# weichen-a-3.net
KiCad netlist of a schematic drawn in EAGLE
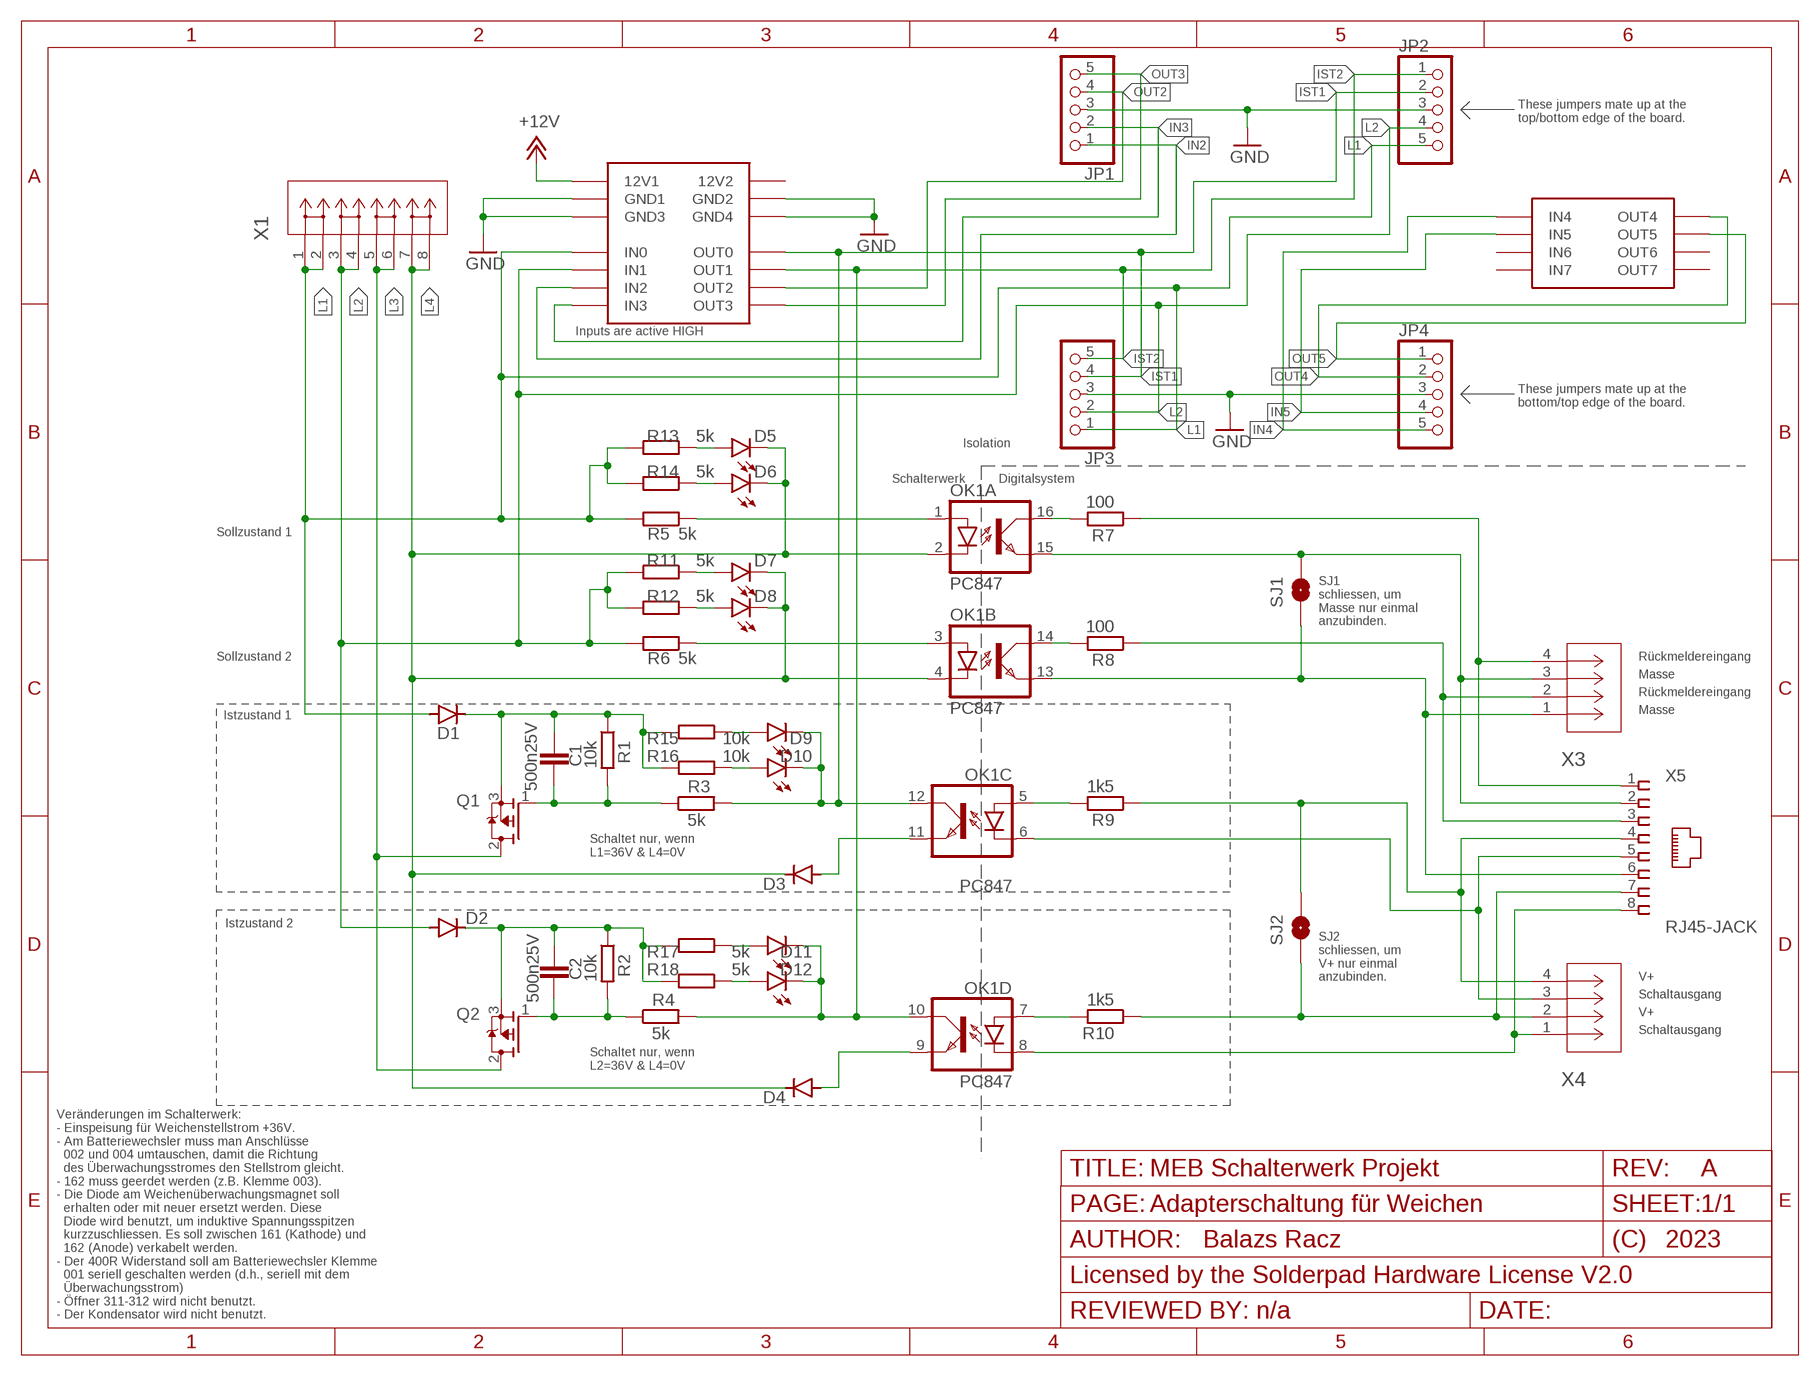
[diagram p0: schematic, sheet 1]

(export (version "E")
  (design (tool "Eeschema 10.0.6"))
  (components
    (comp (ref "C1")
      (value "500n25V")
      (footprint "eagle-import:C0805")
      (libsource (lib "eagle-import") (part "C-EUC0805"))
    )
    (comp (ref "C2")
      (value "500n25V")
      (footprint "eagle-import:C0805")
      (libsource (lib "eagle-import") (part "C-EUC0805"))
    )
    (comp (ref "D1")
      (value "DIODE-DO214AC")
      (footprint "eagle-import:DO214AC")
      (libsource (lib "eagle-import") (part "DIODE-DO214AC"))
    )
    (comp (ref "D2")
      (value "DIODE-DO214AC")
      (footprint "eagle-import:DO214AC")
      (libsource (lib "eagle-import") (part "DIODE-DO214AC"))
    )
    (comp (ref "D3")
      (value "DIODE-MINIMELF")
      (footprint "eagle-import:MINIMELF")
      (libsource (lib "eagle-import") (part "DIODE-MINIMELF"))
    )
    (comp (ref "D4")
      (value "DIODE-MINIMELF")
      (footprint "eagle-import:MINIMELF")
      (libsource (lib "eagle-import") (part "DIODE-MINIMELF"))
    )
    (comp (ref "D5")
      (value "LEDCHIPLED_0603")
      (footprint "eagle-import:CHIPLED_0603")
      (libsource (lib "eagle-import") (part "LEDCHIPLED_0603"))
    )
    (comp (ref "D6")
      (value "LEDHEADER")
      (footprint "eagle-import:LEDHEADER")
      (libsource (lib "eagle-import") (part "LEDHEADER"))
    )
    (comp (ref "D7")
      (value "LEDCHIPLED_0603")
      (footprint "eagle-import:CHIPLED_0603")
      (libsource (lib "eagle-import") (part "LEDCHIPLED_0603"))
    )
    (comp (ref "D8")
      (value "LEDHEADER")
      (footprint "eagle-import:LEDHEADER")
      (libsource (lib "eagle-import") (part "LEDHEADER"))
    )
    (comp (ref "D9")
      (value "LEDCHIPLED_0603")
      (footprint "eagle-import:CHIPLED_0603")
      (libsource (lib "eagle-import") (part "LEDCHIPLED_0603"))
    )
    (comp (ref "D10")
      (value "LEDHEADER")
      (footprint "eagle-import:LEDHEADER")
      (libsource (lib "eagle-import") (part "LEDHEADER"))
    )
    (comp (ref "D11")
      (value "LEDCHIPLED_0603")
      (footprint "eagle-import:CHIPLED_0603")
      (libsource (lib "eagle-import") (part "LEDCHIPLED_0603"))
    )
    (comp (ref "D12")
      (value "LEDHEADER")
      (footprint "eagle-import:LEDHEADER")
      (libsource (lib "eagle-import") (part "LEDHEADER"))
    )
    (comp (ref "JP1")
      (value "PINHD-1X55X2MM")
      (footprint "eagle-import:1_05X2MM")
      (libsource (lib "eagle-import") (part "PINHD-1X55X2MM"))
    )
    (comp (ref "JP2")
      (value "PINHD-1X55X2MM")
      (footprint "eagle-import:1_05X2MM")
      (libsource (lib "eagle-import") (part "PINHD-1X55X2MM"))
    )
    (comp (ref "JP3")
      (value "PINHD-1X55X2MM")
      (footprint "eagle-import:1_05X2MM")
      (libsource (lib "eagle-import") (part "PINHD-1X55X2MM"))
    )
    (comp (ref "JP4")
      (value "PINHD-1X55X2MM")
      (footprint "eagle-import:1_05X2MM")
      (libsource (lib "eagle-import") (part "PINHD-1X55X2MM"))
    )
    (comp (ref "OK1")
      (value "PC847")
      (footprint "eagle-import:DIL16")
      (libsource (lib "eagle-import") (part "PC847"))
    )
    (comp (ref "Q1")
      (value "P-MOSFET")
      (footprint "eagle-import:DPAK-2")
      (fields (field (name "MANUFACTURER") "Infineon"))
      (libsource (lib "eagle-import") (part "P-MOSFET"))
    )
    (comp (ref "Q2")
      (value "P-MOSFET")
      (footprint "eagle-import:DPAK-2")
      (fields (field (name "MANUFACTURER") "Infineon"))
      (libsource (lib "eagle-import") (part "P-MOSFET"))
    )
    (comp (ref "R1")
      (value "10k")
      (footprint "eagle-import:R0805")
      (libsource (lib "eagle-import") (part "R-EU_R0805"))
    )
    (comp (ref "R2")
      (value "10k")
      (footprint "eagle-import:R0805")
      (libsource (lib "eagle-import") (part "R-EU_R0805"))
    )
    (comp (ref "R3")
      (value "5k")
      (footprint "eagle-import:R0805")
      (libsource (lib "eagle-import") (part "R-EU_R0805"))
    )
    (comp (ref "R4")
      (value "5k")
      (footprint "eagle-import:R0805")
      (libsource (lib "eagle-import") (part "R-EU_R0805"))
    )
    (comp (ref "R5")
      (value "5k")
      (footprint "eagle-import:R0805")
      (libsource (lib "eagle-import") (part "R-EU_R0805"))
    )
    (comp (ref "R6")
      (value "5k")
      (footprint "eagle-import:R0805")
      (libsource (lib "eagle-import") (part "R-EU_R0805"))
    )
    (comp (ref "R7")
      (value "100")
      (footprint "eagle-import:R0805")
      (libsource (lib "eagle-import") (part "R-EU_R0805"))
    )
    (comp (ref "R8")
      (value "100")
      (footprint "eagle-import:R0805")
      (libsource (lib "eagle-import") (part "R-EU_R0805"))
    )
    (comp (ref "R9")
      (value "1k5")
      (footprint "eagle-import:R0805")
      (libsource (lib "eagle-import") (part "R-EU_R0805"))
    )
    (comp (ref "R10")
      (value "1k5")
      (footprint "eagle-import:R0805")
      (libsource (lib "eagle-import") (part "R-EU_R0805"))
    )
    (comp (ref "R11")
      (value "5k")
      (footprint "eagle-import:R0805")
      (libsource (lib "eagle-import") (part "R-EU_R0805"))
    )
    (comp (ref "R12")
      (value "5k")
      (footprint "eagle-import:R0805")
      (libsource (lib "eagle-import") (part "R-EU_R0805"))
    )
    (comp (ref "R13")
      (value "5k")
      (footprint "eagle-import:R0805")
      (libsource (lib "eagle-import") (part "R-EU_R0805"))
    )
    (comp (ref "R14")
      (value "5k")
      (footprint "eagle-import:R0805")
      (libsource (lib "eagle-import") (part "R-EU_R0805"))
    )
    (comp (ref "R15")
      (value "10k")
      (footprint "eagle-import:R0805")
      (libsource (lib "eagle-import") (part "R-EU_R0805"))
    )
    (comp (ref "R16")
      (value "10k")
      (footprint "eagle-import:R0805")
      (libsource (lib "eagle-import") (part "R-EU_R0805"))
    )
    (comp (ref "R17")
      (value "5k")
      (footprint "eagle-import:R0805")
      (libsource (lib "eagle-import") (part "R-EU_R0805"))
    )
    (comp (ref "R18")
      (value "5k")
      (footprint "eagle-import:R0805")
      (libsource (lib "eagle-import") (part "R-EU_R0805"))
    )
    (comp (ref "SJ1")
      (value "SJRND2")
      (footprint "eagle-import:SJ_RND2")
      (libsource (lib "eagle-import") (part "SJRND2"))
    )
    (comp (ref "SJ2")
      (value "SJRND2")
      (footprint "eagle-import:SJ_RND2")
      (libsource (lib "eagle-import") (part "SJRND2"))
    )
    (comp (ref "X1")
      (value "PHNX_4P_508CONN_1017493")
      (footprint "eagle-import:PHNX_4P_508")
      (fields
        (field (name "MANUFACTURER_PART_NUMBER") "1017505")
        (field (name "COPYRIGHT") "Copyright (C) 2023 Ultra Librarian. All rights reserved.")
      )
      (libsource (lib "eagle-import") (part "PHNX_4P_508CONN_1017493"))
    )
    (comp (ref "X2")
      (value "IO-HAT")
      (footprint "eagle-import:IOBOARD")
      (libsource (lib "eagle-import") (part "IO-HAT"))
    )
    (comp (ref "X3")
      (value "PHNX_4P_350CONN_1984989_PXC")
      (footprint "eagle-import:PHNX_4P_350")
      (fields
        (field (name "MANUFACTURER_PART_NUMBER") "1984989")
        (field (name "COPYRIGHT") "Copyright (C) 2023 Ultra Librarian. All rights reserved.")
      )
      (libsource (lib "eagle-import") (part "PHNX_4P_350CONN_1984989_PXC"))
    )
    (comp (ref "X4")
      (value "PHNX_4P_350CONN_1984989_PXC")
      (footprint "eagle-import:PHNX_4P_350")
      (fields
        (field (name "MANUFACTURER_PART_NUMBER") "1984989")
        (field (name "COPYRIGHT") "Copyright (C) 2023 Ultra Librarian. All rights reserved.")
      )
      (libsource (lib "eagle-import") (part "PHNX_4P_350CONN_1984989_PXC"))
    )
    (comp (ref "X5")
      (value "RJ45-JACK")
      (footprint "eagle-import:RJ45-PULSE-E5J88")
      (libsource (lib "eagle-import") (part "RJ45-JACKRJ45-PULSE-E5J00"))
    )
  )
  (nets
    (net (code "1") (name "+12V") (class "Default")
      (node (ref "X2") (pin "P$1") (pinfunction "12V1_P$1") (pintype "power_in"))
    )
    (net (code "2") (name "/12V2") (class "Default")
      (node (ref "X2") (pin "P$22") (pinfunction "12V2_P$22") (pintype "power_in"))
    )
    (net (code "3") (name "GND") (class "Default")
      (node (ref "JP1") (pin "3") (pinfunction "3_3") (pintype "passive"))
      (node (ref "JP2") (pin "3") (pinfunction "3_3") (pintype "passive"))
      (node (ref "JP3") (pin "3") (pinfunction "3_3") (pintype "passive"))
      (node (ref "JP4") (pin "3") (pinfunction "3_3") (pintype "passive"))
      (node (ref "X2") (pin "P$11") (pinfunction "GND3_P$11") (pintype "power_in"))
      (node (ref "X2") (pin "P$12") (pinfunction "GND4_P$12") (pintype "power_in"))
      (node (ref "X2") (pin "P$2") (pinfunction "GND1_P$2") (pintype "power_in"))
      (node (ref "X2") (pin "P$21") (pinfunction "GND2_P$21") (pintype "power_in"))
    )
    (net (code "4") (name "IN2") (class "Default")
      (node (ref "JP1") (pin "1") (pinfunction "1_1") (pintype "passive"))
      (node (ref "X2") (pin "P$5") (pinfunction "IN2_P$5") (pintype "input"))
    )
    (net (code "5") (name "IN3") (class "Default")
      (node (ref "JP1") (pin "2") (pinfunction "2_2") (pintype "passive"))
      (node (ref "X2") (pin "P$6") (pinfunction "IN3_P$6") (pintype "input"))
    )
    (net (code "6") (name "IN4") (class "Default")
      (node (ref "JP4") (pin "5") (pinfunction "5_5") (pintype "passive"))
      (node (ref "X2") (pin "P$7") (pinfunction "IN4_P$7") (pintype "input"))
    )
    (net (code "7") (name "IN5") (class "Default")
      (node (ref "JP4") (pin "4") (pinfunction "4_4") (pintype "passive"))
      (node (ref "X2") (pin "P$8") (pinfunction "IN5_P$8") (pintype "input"))
    )
    (net (code "8") (name "IST1") (class "Default")
      (node (ref "D10") (pin "C") (pinfunction "C_C") (pintype "passive"))
      (node (ref "D9") (pin "C") (pinfunction "C_C") (pintype "passive"))
      (node (ref "JP2") (pin "2") (pinfunction "2_2") (pintype "passive"))
      (node (ref "JP3") (pin "4") (pinfunction "4_4") (pintype "passive"))
      (node (ref "OK1") (pin "12") (pinfunction "COL_12") (pintype "passive"))
      (node (ref "R3") (pin "2") (pinfunction "2_2") (pintype "passive"))
      (node (ref "X2") (pin "P$20") (pinfunction "OUT0_P$20") (pintype "open_collector"))
    )
    (net (code "9") (name "IST2") (class "Default")
      (node (ref "D11") (pin "C") (pinfunction "C_C") (pintype "passive"))
      (node (ref "D12") (pin "C") (pinfunction "C_C") (pintype "passive"))
      (node (ref "JP2") (pin "1") (pinfunction "1_1") (pintype "passive"))
      (node (ref "JP3") (pin "5") (pinfunction "5_5") (pintype "passive"))
      (node (ref "OK1") (pin "10") (pinfunction "COL_10") (pintype "passive"))
      (node (ref "R4") (pin "2") (pinfunction "2_2") (pintype "passive"))
      (node (ref "X2") (pin "P$19") (pinfunction "OUT1_P$19") (pintype "open_collector"))
    )
    (net (code "10") (name "L1") (class "Default")
      (node (ref "D1") (pin "A") (pinfunction "A_A") (pintype "passive"))
      (node (ref "JP2") (pin "5") (pinfunction "5_5") (pintype "passive"))
      (node (ref "JP3") (pin "1") (pinfunction "1_1") (pintype "passive"))
      (node (ref "R13") (pin "2") (pinfunction "2_2") (pintype "passive"))
      (node (ref "R14") (pin "2") (pinfunction "2_2") (pintype "passive"))
      (node (ref "R5") (pin "2") (pinfunction "2_2") (pintype "passive"))
      (node (ref "X1") (pin "1") (pinfunction "1_1") (pintype "passive"))
      (node (ref "X1") (pin "2") (pinfunction "2_2") (pintype "passive"))
      (node (ref "X2") (pin "P$3") (pinfunction "IN0_P$3") (pintype "input"))
    )
    (net (code "11") (name "L2") (class "Default")
      (node (ref "D2") (pin "A") (pinfunction "A_A") (pintype "passive"))
      (node (ref "JP2") (pin "4") (pinfunction "4_4") (pintype "passive"))
      (node (ref "JP3") (pin "2") (pinfunction "2_2") (pintype "passive"))
      (node (ref "R11") (pin "2") (pinfunction "2_2") (pintype "passive"))
      (node (ref "R12") (pin "2") (pinfunction "2_2") (pintype "passive"))
      (node (ref "R6") (pin "2") (pinfunction "2_2") (pintype "passive"))
      (node (ref "X1") (pin "3") (pinfunction "3_3") (pintype "passive"))
      (node (ref "X1") (pin "4") (pinfunction "4_4") (pintype "passive"))
      (node (ref "X2") (pin "P$4") (pinfunction "IN1_P$4") (pintype "input"))
    )
    (net (code "12") (name "L3") (class "Default")
      (node (ref "Q1") (pin "2") (pinfunction "D_2") (pintype "passive"))
      (node (ref "Q2") (pin "2") (pinfunction "D_2") (pintype "passive"))
      (node (ref "X1") (pin "5") (pinfunction "5_5") (pintype "passive"))
      (node (ref "X1") (pin "6") (pinfunction "6_6") (pintype "passive"))
    )
    (net (code "13") (name "L4") (class "Default")
      (node (ref "D3") (pin "C") (pinfunction "C_C") (pintype "passive"))
      (node (ref "D4") (pin "C") (pinfunction "C_C") (pintype "passive"))
      (node (ref "D5") (pin "C") (pinfunction "C_C") (pintype "passive"))
      (node (ref "D6") (pin "C") (pinfunction "C_C") (pintype "passive"))
      (node (ref "D7") (pin "C") (pinfunction "C_C") (pintype "passive"))
      (node (ref "D8") (pin "C") (pinfunction "C_C") (pintype "passive"))
      (node (ref "OK1") (pin "2") (pinfunction "C_2") (pintype "passive"))
      (node (ref "OK1") (pin "4") (pinfunction "C_4") (pintype "passive"))
      (node (ref "X1") (pin "7") (pinfunction "7_7") (pintype "passive"))
      (node (ref "X1") (pin "8") (pinfunction "8_8") (pintype "passive"))
    )
    (net (code "14") (name "Net-(D5-PadA)") (class "Default")
      (node (ref "D5") (pin "A") (pinfunction "A_A") (pintype "passive"))
      (node (ref "R13") (pin "1") (pinfunction "1_1") (pintype "passive"))
    )
    (net (code "15") (name "Net-(D6-PadA)") (class "Default")
      (node (ref "D6") (pin "A") (pinfunction "A_A") (pintype "passive"))
      (node (ref "R14") (pin "1") (pinfunction "1_1") (pintype "passive"))
    )
    (net (code "16") (name "Net-(D7-PadA)") (class "Default")
      (node (ref "D7") (pin "A") (pinfunction "A_A") (pintype "passive"))
      (node (ref "R11") (pin "1") (pinfunction "1_1") (pintype "passive"))
    )
    (net (code "17") (name "Net-(D8-PadA)") (class "Default")
      (node (ref "D8") (pin "A") (pinfunction "A_A") (pintype "passive"))
      (node (ref "R12") (pin "1") (pinfunction "1_1") (pintype "passive"))
    )
    (net (code "18") (name "Net-(D9-PadA)") (class "Default")
      (node (ref "D9") (pin "A") (pinfunction "A_A") (pintype "passive"))
      (node (ref "R15") (pin "1") (pinfunction "1_1") (pintype "passive"))
    )
    (net (code "19") (name "Net-(D10-PadA)") (class "Default")
      (node (ref "D10") (pin "A") (pinfunction "A_A") (pintype "passive"))
      (node (ref "R16") (pin "1") (pinfunction "1_1") (pintype "passive"))
    )
    (net (code "20") (name "Net-(D11-PadA)") (class "Default")
      (node (ref "D11") (pin "A") (pinfunction "A_A") (pintype "passive"))
      (node (ref "R17") (pin "1") (pinfunction "1_1") (pintype "passive"))
    )
    (net (code "21") (name "Net-(D12-PadA)") (class "Default")
      (node (ref "D12") (pin "A") (pinfunction "A_A") (pintype "passive"))
      (node (ref "R18") (pin "1") (pinfunction "1_1") (pintype "passive"))
    )
    (net (code "22") (name "Net-(OK1A-A)") (class "Default")
      (node (ref "OK1") (pin "1") (pinfunction "A_1") (pintype "passive"))
      (node (ref "R5") (pin "1") (pinfunction "1_1") (pintype "passive"))
    )
    (net (code "23") (name "Net-(OK1A-COL)") (class "Default")
      (node (ref "OK1") (pin "16") (pinfunction "COL_16") (pintype "passive"))
      (node (ref "R7") (pin "2") (pinfunction "2_2") (pintype "passive"))
    )
    (net (code "24") (name "Net-(OK1A-EMIT)") (class "Default")
      (node (ref "OK1") (pin "15") (pinfunction "EMIT_15") (pintype "passive"))
      (node (ref "SJ1") (pin "P$2") (pinfunction "2_P$2") (pintype "passive"))
      (node (ref "X3") (pin "3") (pinfunction "3_3") (pintype "passive"))
      (node (ref "X5") (pin "2") (pinfunction "2_2") (pintype "passive"))
    )
    (net (code "25") (name "Net-(OK1B-A)") (class "Default")
      (node (ref "OK1") (pin "3") (pinfunction "A_3") (pintype "passive"))
      (node (ref "R6") (pin "1") (pinfunction "1_1") (pintype "passive"))
    )
    (net (code "26") (name "Net-(OK1B-COL)") (class "Default")
      (node (ref "OK1") (pin "14") (pinfunction "COL_14") (pintype "passive"))
      (node (ref "R8") (pin "2") (pinfunction "2_2") (pintype "passive"))
    )
    (net (code "27") (name "Net-(OK1B-EMIT)") (class "Default")
      (node (ref "OK1") (pin "13") (pinfunction "EMIT_13") (pintype "passive"))
      (node (ref "SJ1") (pin "P$1") (pinfunction "1_P$1") (pintype "passive"))
      (node (ref "X3") (pin "1") (pinfunction "1_1") (pintype "passive"))
      (node (ref "X5") (pin "6") (pinfunction "6_6") (pintype "passive"))
    )
    (net (code "28") (name "Net-(OK1C-A)") (class "Default")
      (node (ref "OK1") (pin "5") (pinfunction "A_5") (pintype "passive"))
      (node (ref "R9") (pin "2") (pinfunction "2_2") (pintype "passive"))
    )
    (net (code "29") (name "Net-(OK1C-C)") (class "Default")
      (node (ref "OK1") (pin "6") (pinfunction "C_6") (pintype "passive"))
      (node (ref "X4") (pin "3") (pinfunction "3_3") (pintype "passive"))
      (node (ref "X5") (pin "5") (pinfunction "5_5") (pintype "passive"))
    )
    (net (code "30") (name "Net-(OK1C-EMIT)") (class "Default")
      (node (ref "D3") (pin "A") (pinfunction "A_A") (pintype "passive"))
      (node (ref "OK1") (pin "11") (pinfunction "EMIT_11") (pintype "passive"))
    )
    (net (code "31") (name "Net-(OK1D-A)") (class "Default")
      (node (ref "OK1") (pin "7") (pinfunction "A_7") (pintype "passive"))
      (node (ref "R10") (pin "2") (pinfunction "2_2") (pintype "passive"))
    )
    (net (code "32") (name "Net-(OK1D-C)") (class "Default")
      (node (ref "OK1") (pin "8") (pinfunction "C_8") (pintype "passive"))
      (node (ref "X4") (pin "1") (pinfunction "1_1") (pintype "passive"))
      (node (ref "X5") (pin "8") (pinfunction "8_8") (pintype "passive"))
    )
    (net (code "33") (name "Net-(OK1D-EMIT)") (class "Default")
      (node (ref "D4") (pin "A") (pinfunction "A_A") (pintype "passive"))
      (node (ref "OK1") (pin "9") (pinfunction "EMIT_9") (pintype "passive"))
    )
    (net (code "34") (name "Net-(Q1-G)") (class "Default")
      (node (ref "C1") (pin "2") (pinfunction "2_2") (pintype "passive"))
      (node (ref "Q1") (pin "1") (pinfunction "G_1") (pintype "passive"))
      (node (ref "R1") (pin "2") (pinfunction "2_2") (pintype "passive"))
      (node (ref "R3") (pin "1") (pinfunction "1_1") (pintype "passive"))
    )
    (net (code "35") (name "Net-(Q1-S)") (class "Default")
      (node (ref "C1") (pin "1") (pinfunction "1_1") (pintype "passive"))
      (node (ref "D1") (pin "C") (pinfunction "C_C") (pintype "passive"))
      (node (ref "Q1") (pin "3") (pinfunction "S_3") (pintype "passive"))
      (node (ref "R1") (pin "1") (pinfunction "1_1") (pintype "passive"))
      (node (ref "R15") (pin "2") (pinfunction "2_2") (pintype "passive"))
      (node (ref "R16") (pin "2") (pinfunction "2_2") (pintype "passive"))
    )
    (net (code "36") (name "Net-(Q2-G)") (class "Default")
      (node (ref "C2") (pin "2") (pinfunction "2_2") (pintype "passive"))
      (node (ref "Q2") (pin "1") (pinfunction "G_1") (pintype "passive"))
      (node (ref "R2") (pin "2") (pinfunction "2_2") (pintype "passive"))
      (node (ref "R4") (pin "1") (pinfunction "1_1") (pintype "passive"))
    )
    (net (code "37") (name "Net-(Q2-S)") (class "Default")
      (node (ref "C2") (pin "1") (pinfunction "1_1") (pintype "passive"))
      (node (ref "D2") (pin "C") (pinfunction "C_C") (pintype "passive"))
      (node (ref "Q2") (pin "3") (pinfunction "S_3") (pintype "passive"))
      (node (ref "R17") (pin "2") (pinfunction "2_2") (pintype "passive"))
      (node (ref "R18") (pin "2") (pinfunction "2_2") (pintype "passive"))
      (node (ref "R2") (pin "1") (pinfunction "1_1") (pintype "passive"))
    )
    (net (code "38") (name "Net-(R7-Pad1)") (class "Default")
      (node (ref "R7") (pin "1") (pinfunction "1_1") (pintype "passive"))
      (node (ref "X3") (pin "4") (pinfunction "4_4") (pintype "passive"))
      (node (ref "X5") (pin "1") (pinfunction "1_1") (pintype "passive"))
    )
    (net (code "39") (name "Net-(R8-Pad1)") (class "Default")
      (node (ref "R8") (pin "1") (pinfunction "1_1") (pintype "passive"))
      (node (ref "X3") (pin "2") (pinfunction "2_2") (pintype "passive"))
      (node (ref "X5") (pin "3") (pinfunction "3_3") (pintype "passive"))
    )
    (net (code "40") (name "Net-(SJ2-1)") (class "Default")
      (node (ref "R10") (pin "1") (pinfunction "1_1") (pintype "passive"))
      (node (ref "SJ2") (pin "P$1") (pinfunction "1_P$1") (pintype "passive"))
      (node (ref "X4") (pin "2") (pinfunction "2_2") (pintype "passive"))
      (node (ref "X5") (pin "7") (pinfunction "7_7") (pintype "passive"))
    )
    (net (code "41") (name "Net-(SJ2-2)") (class "Default")
      (node (ref "R9") (pin "1") (pinfunction "1_1") (pintype "passive"))
      (node (ref "SJ2") (pin "P$2") (pinfunction "2_P$2") (pintype "passive"))
      (node (ref "X4") (pin "4") (pinfunction "4_4") (pintype "passive"))
      (node (ref "X5") (pin "4") (pinfunction "4_4") (pintype "passive"))
    )
    (net (code "42") (name "OUT2") (class "Default")
      (node (ref "JP1") (pin "4") (pinfunction "4_4") (pintype "passive"))
      (node (ref "X2") (pin "P$18") (pinfunction "OUT2_P$18") (pintype "open_collector"))
    )
    (net (code "43") (name "OUT3") (class "Default")
      (node (ref "JP1") (pin "5") (pinfunction "5_5") (pintype "passive"))
      (node (ref "X2") (pin "P$17") (pinfunction "OUT3_P$17") (pintype "open_collector"))
    )
    (net (code "44") (name "OUT4") (class "Default")
      (node (ref "JP4") (pin "2") (pinfunction "2_2") (pintype "passive"))
      (node (ref "X2") (pin "P$16") (pinfunction "OUT4_P$16") (pintype "open_collector"))
    )
    (net (code "45") (name "OUT5") (class "Default")
      (node (ref "JP4") (pin "1") (pinfunction "1_1") (pintype "passive"))
      (node (ref "X2") (pin "P$15") (pinfunction "OUT5_P$15") (pintype "open_collector"))
    )
    (net (code "46") (name "unconnected-(X2B-IN6-PadP$9)") (class "Default")
      (node (ref "X2") (pin "P$9") (pinfunction "IN6_P$9") (pintype "input"))
    )
    (net (code "47") (name "unconnected-(X2B-IN7-PadP$10)") (class "Default")
      (node (ref "X2") (pin "P$10") (pinfunction "IN7_P$10") (pintype "input"))
    )
    (net (code "48") (name "unconnected-(X2B-OUT6-PadP$14)") (class "Default")
      (node (ref "X2") (pin "P$14") (pinfunction "OUT6_P$14") (pintype "open_collector"))
    )
    (net (code "49") (name "unconnected-(X2B-OUT7-PadP$13)") (class "Default")
      (node (ref "X2") (pin "P$13") (pinfunction "OUT7_P$13") (pintype "open_collector"))
    )
  )
)
